# IP.net
KiCad netlist of a schematic drawn in Altium Designer
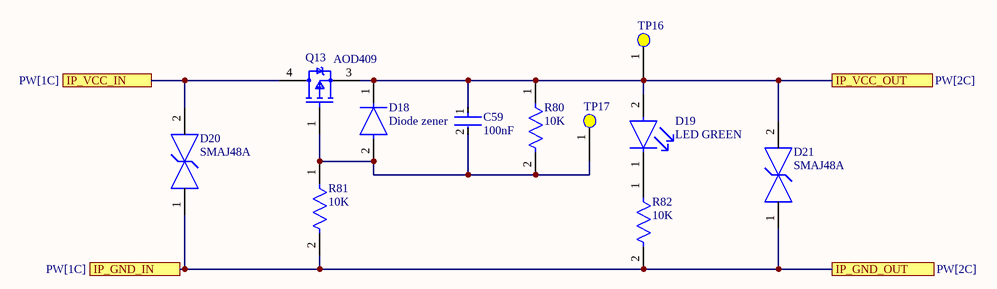
[diagram p0: IP.SchDoc]

(export (version "E")
  (design (tool "Eeschema 10.0.6"))
  (components
    (comp (ref "C59")
      (value "100nF")
      (footprint "FP-GRM18-0_15-MFG")
      (description "CAP CER 10V X5R 0603")
      (fields
        (field (name "OCTOPART") "https://octopart.com/grm188r61a106ke69d-murata-22851381")
        (field (name "MANUFACTURER PART NUMBER") "GRM188R61A106KE69D")
      )
      (libsource (lib "Altium Content Vault") (part "11868f565c42a9108669ba33697ecf6"))
    )
    (comp (ref "D18")
      (value "Diode zener")
      (footprint "FP-DO-213AA-MFG")
      (description "ZMM12 Diode zener 0.5W 12V SOD-80(1206)")
      (fields
        (field (name "OCTOPART") "https://octopart.com/jantx1n4148ur-1-microsemi-6804654")
        (field (name "MANUFACTURER PART NUMBER") "JANTX1N4148UR-1")
      )
      (libsource (lib "Altium Content Vault") (part "d7152d700b627762746794eb795d46e"))
    )
    (comp (ref "D19")
      (value "LED GREEN")
      (footprint "FP-LTST-C190GKT-MFG")
      (description "LED GREEN CLEAR CHIP SMD")
      (fields (field (name "VOLTAGE") "2V"))
      (libsource (lib "Altium Content Vault") (part "8706943c75ba83719d021d2fdc84c58"))
    )
    (comp (ref "D20")
      (value "SMAJ48A")
      (footprint "FP-SMAJ-MFG")
      (description "SMAJ48A TVS DIODE 48VWM 77.4VC DO214AC (SMA)")
      (fields
        (field (name "OCTOPART") "https://octopart.com/smaj58ca-littelfuse-350202")
        (field (name "MANUFACTURER") "Littelfuse Inc")
      )
      (libsource (lib "Altium Content Vault") (part "89c663e49c8877d2c9d183c2997548d"))
    )
    (comp (ref "D21")
      (value "SMAJ48A")
      (footprint "FP-SMAJ-MFG")
      (description "SMAJ48A TVS DIODE 48VWM 77.4VC DO214AC (SMA)")
      (fields
        (field (name "OCTOPART") "https://octopart.com/smaj58ca-littelfuse-350202")
        (field (name "MANUFACTURER") "Littelfuse Inc")
      )
      (libsource (lib "Altium Content Vault") (part "89c663e49c8877d2c9d183c2997548d"))
    )
    (comp (ref "Q13")
      (value "AOD409")
      (footprint "FP-PG-TO252-3-MFG")
      (description "AOD409 MOSFET P-CH 60V 26A TO252")
      (fields
        (field (name "MANUFACTURER") "Infineon")
        (field (name "OCTOPART") "https://octopart.com/irfr5410trpbf-infineon-65874169")
      )
      (libsource (lib "Altium Content Vault") (part "84bd51c0c313388725e75e773aba525"))
    )
    (comp (ref "R80")
      (value "10K")
      (footprint "FP-RC0603-0_55-IPC_A")
      (description "RES 10K OHM 1% 1/10W 0603")
      (fields (field (name "TOLERANCE") "1%"))
      (libsource (lib "Altium Content Vault") (part "1029c3af85768c4190bb7ad29bc67b5"))
    )
    (comp (ref "R81")
      (value "10K")
      (footprint "FP-RC0603-0_55-IPC_C")
      (description "RES 10K OHM 1% 1/10W 0603")
      (fields (field (name "TOLERANCE") "1%"))
      (libsource (lib "Altium Content Vault") (part "1029c3af85768c4190bb7ad29bc67b5"))
    )
    (comp (ref "R82")
      (value "10K")
      (footprint "FP-RC0603-0_55-IPC_C")
      (description "RES 10K OHM 1% 1/10W 0603")
      (fields (field (name "TOLERANCE") "1%"))
      (libsource (lib "Altium Content Vault") (part "1029c3af85768c4190bb7ad29bc67b5"))
    )
    (comp (ref "TP16")
      (value "Test Point")
      (footprint "Test Point")
      (libsource (lib "atlab_altium_lib") (part "Test Point"))
    )
    (comp (ref "TP17")
      (value "Test Point")
      (footprint "Test Point")
      (libsource (lib "atlab_altium_lib") (part "Test Point"))
    )
  )
  (nets
    (net (code "1") (name "/IP_GND_IN") (class "Default")
      (node (ref "D20") (pin "1") (pinfunction "1_1") (pintype "passive"))
      (node (ref "D21") (pin "1") (pinfunction "1_1") (pintype "passive"))
      (node (ref "R81") (pin "2") (pinfunction "2_2") (pintype "passive"))
      (node (ref "R82") (pin "2") (pinfunction "2_2") (pintype "passive"))
    )
    (net (code "2") (name "/IP_VCC_IN") (class "Default")
      (node (ref "D20") (pin "2") (pinfunction "2_2") (pintype "passive"))
      (node (ref "Q13") (pin "4") (pinfunction "D_4") (pintype "passive"))
    )
    (net (code "3") (name "/IP_VCC_OUT") (class "Default")
      (node (ref "C59") (pin "1") (pinfunction "1_1") (pintype "passive"))
      (node (ref "D18") (pin "1") (pinfunction "C_1") (pintype "passive"))
      (node (ref "D19") (pin "2") (pinfunction "A_2") (pintype "passive"))
      (node (ref "D21") (pin "2") (pinfunction "2_2") (pintype "passive"))
      (node (ref "Q13") (pin "3") (pinfunction "S_3") (pintype "passive"))
      (node (ref "R80") (pin "1") (pinfunction "1_1") (pintype "passive"))
      (node (ref "TP16") (pin "1") (pinfunction "Test_Point_1") (pintype "passive"))
    )
    (net (code "4") (name "Net-(D18-A)") (class "Default")
      (node (ref "C59") (pin "2") (pinfunction "2_2") (pintype "passive"))
      (node (ref "D18") (pin "2") (pinfunction "A_2") (pintype "passive"))
      (node (ref "Q13") (pin "1") (pinfunction "G_1") (pintype "passive"))
      (node (ref "R80") (pin "2") (pinfunction "2_2") (pintype "passive"))
      (node (ref "R81") (pin "1") (pinfunction "1_1") (pintype "passive"))
      (node (ref "TP17") (pin "1") (pinfunction "Test_Point_1") (pintype "passive"))
    )
    (net (code "5") (name "Net-(D19-C)") (class "Default")
      (node (ref "D19") (pin "1") (pinfunction "C_1") (pintype "passive"))
      (node (ref "R82") (pin "1") (pinfunction "1_1") (pintype "passive"))
    )
  )
)
